# Antennaboard_AndesiteV3Rel.net
KiCad netlist of a schematic drawn in EAGLE
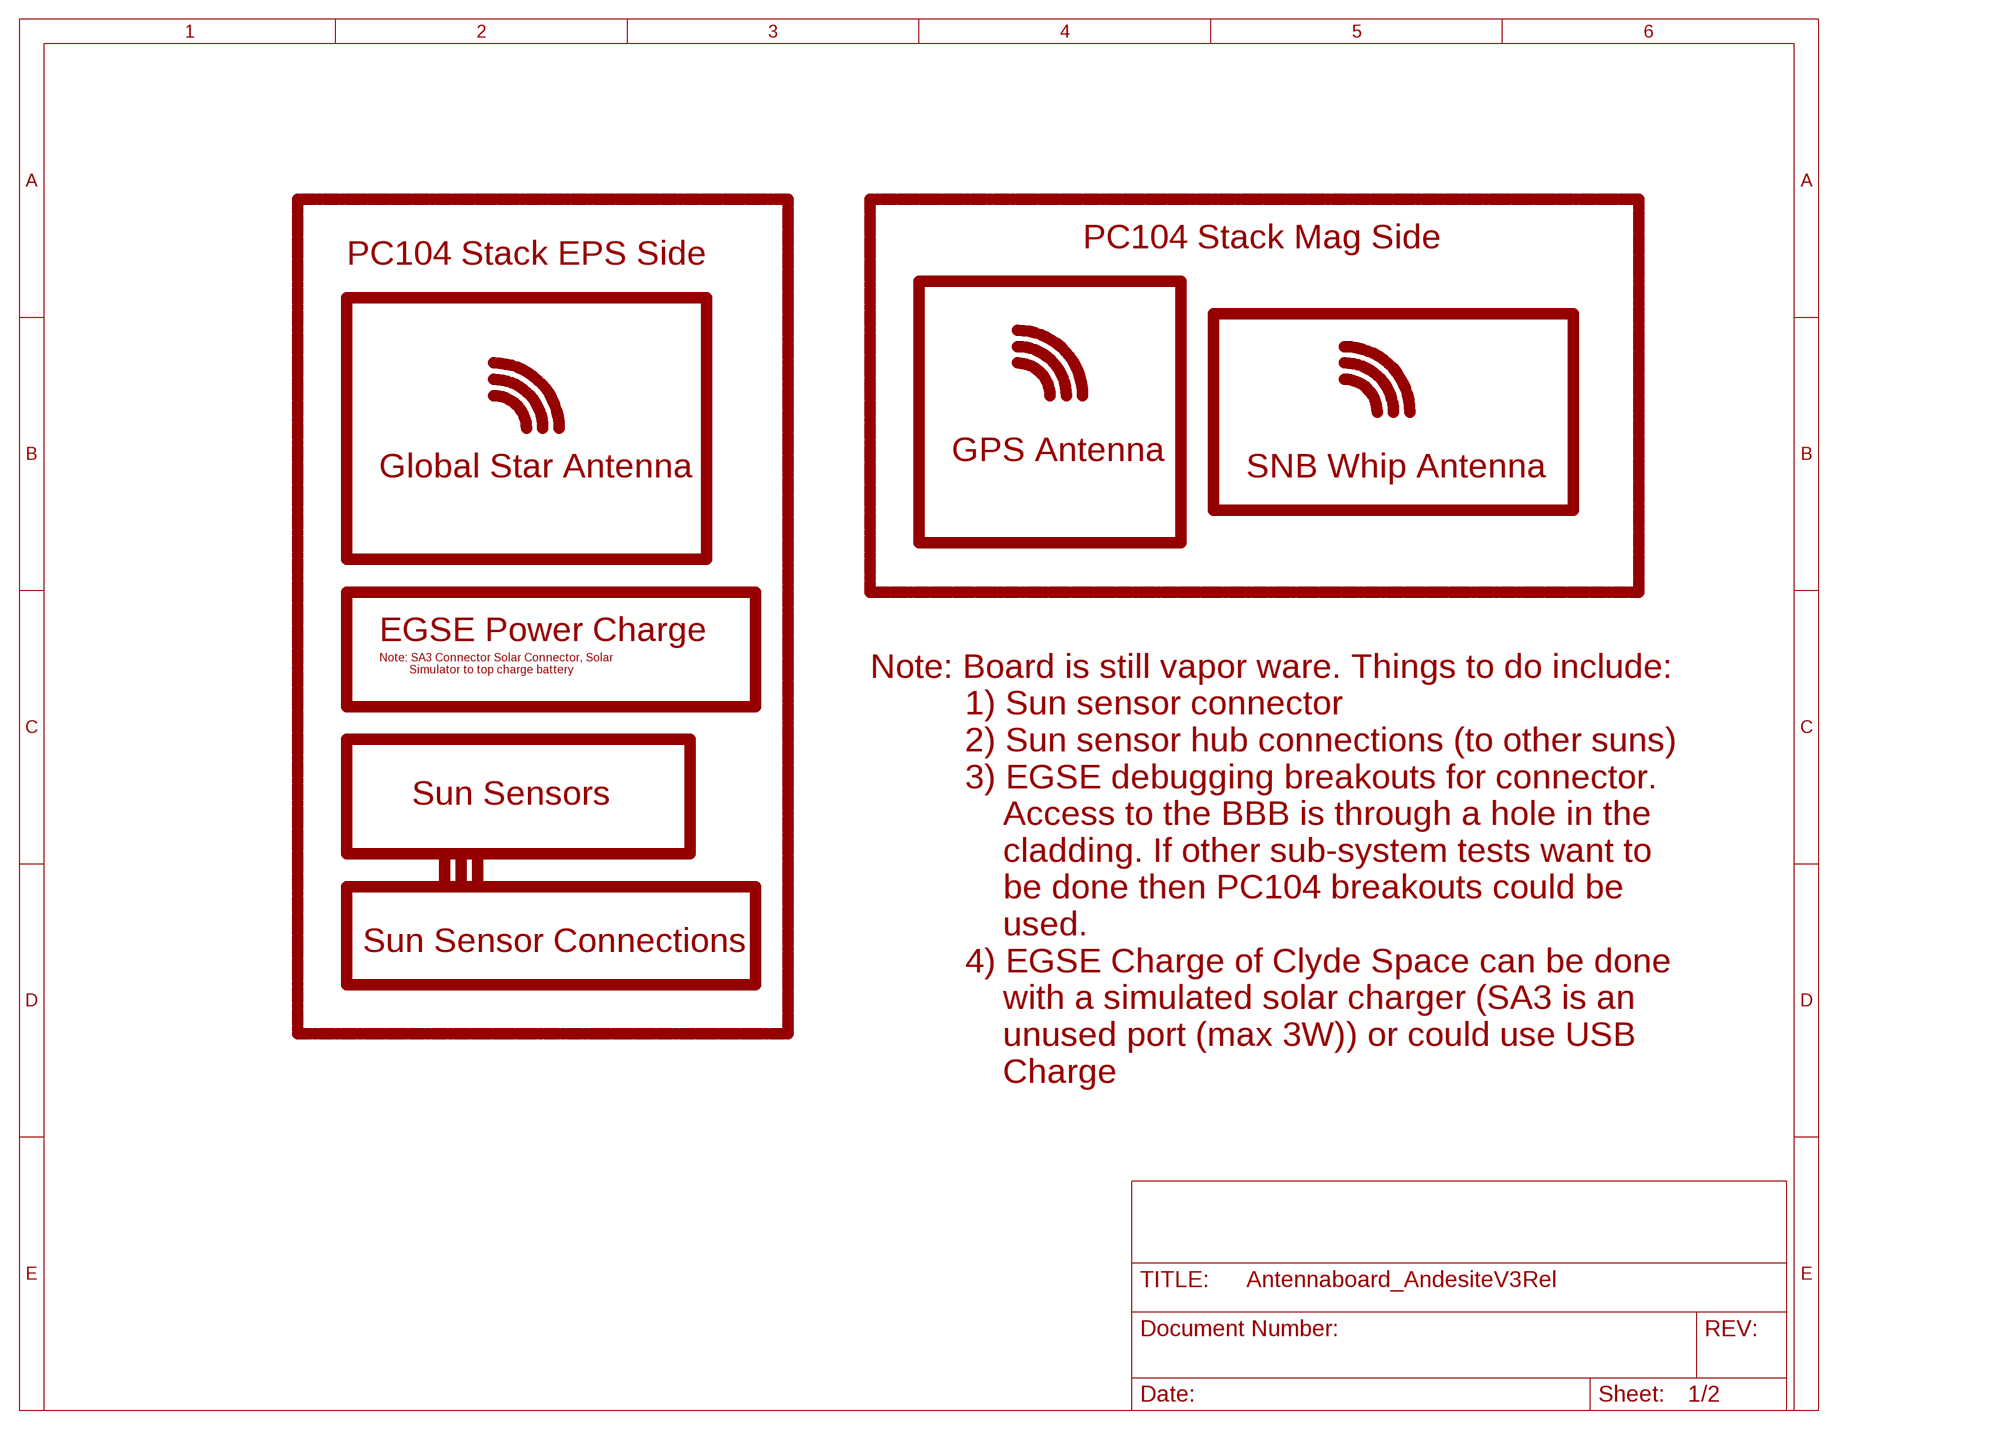
[diagram p0: schematic, sheet 1]
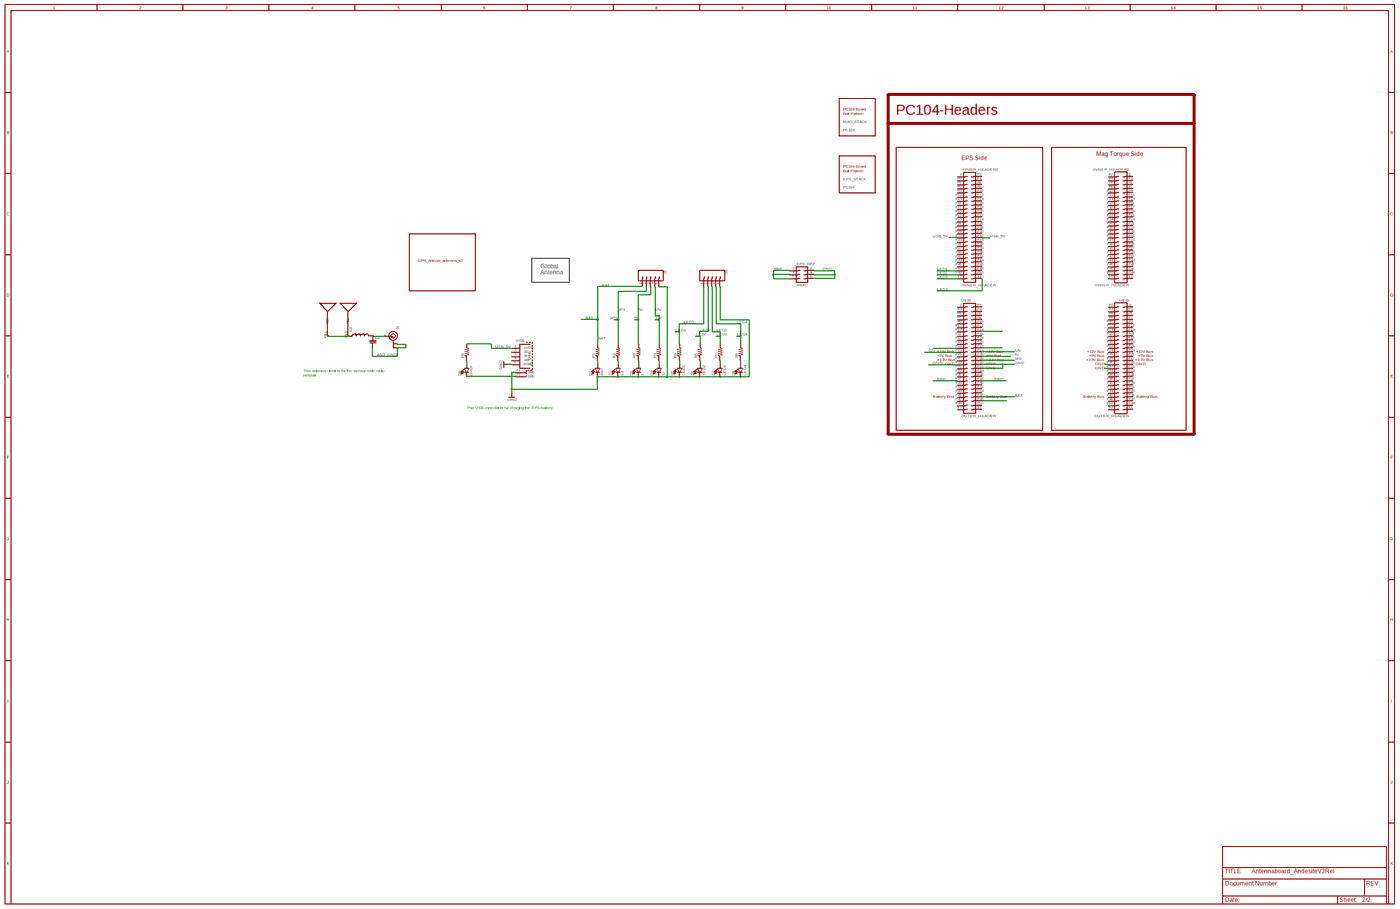
[diagram p1: schematic, sheet 2, overview]
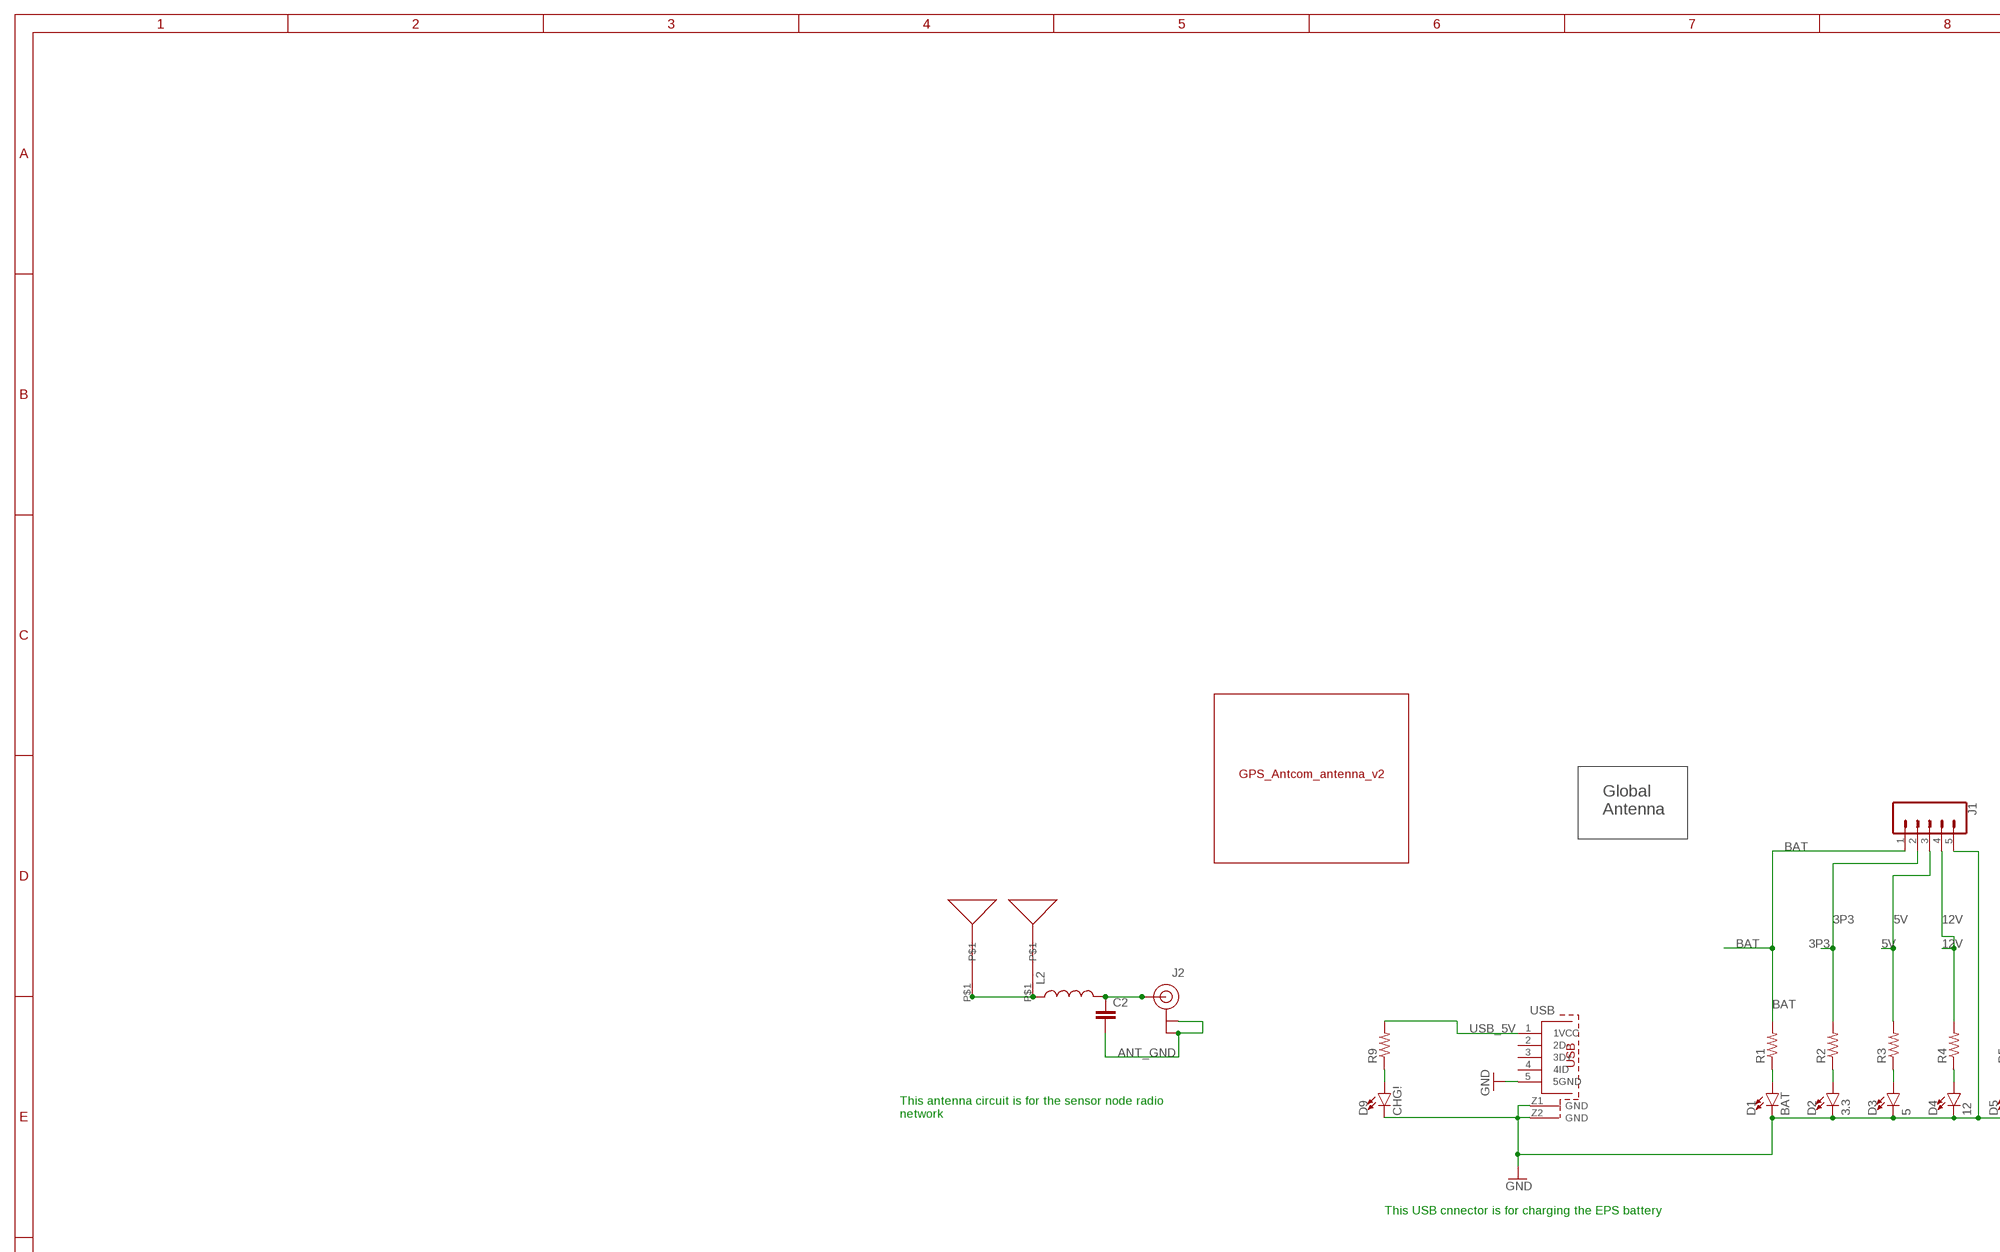
[diagram p2: schematic, sheet 2, part 1 of 4]
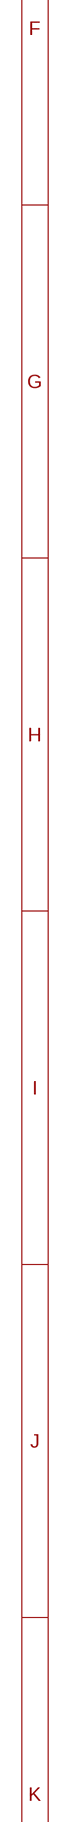
[diagram p3: schematic, sheet 2, part 2 of 4]
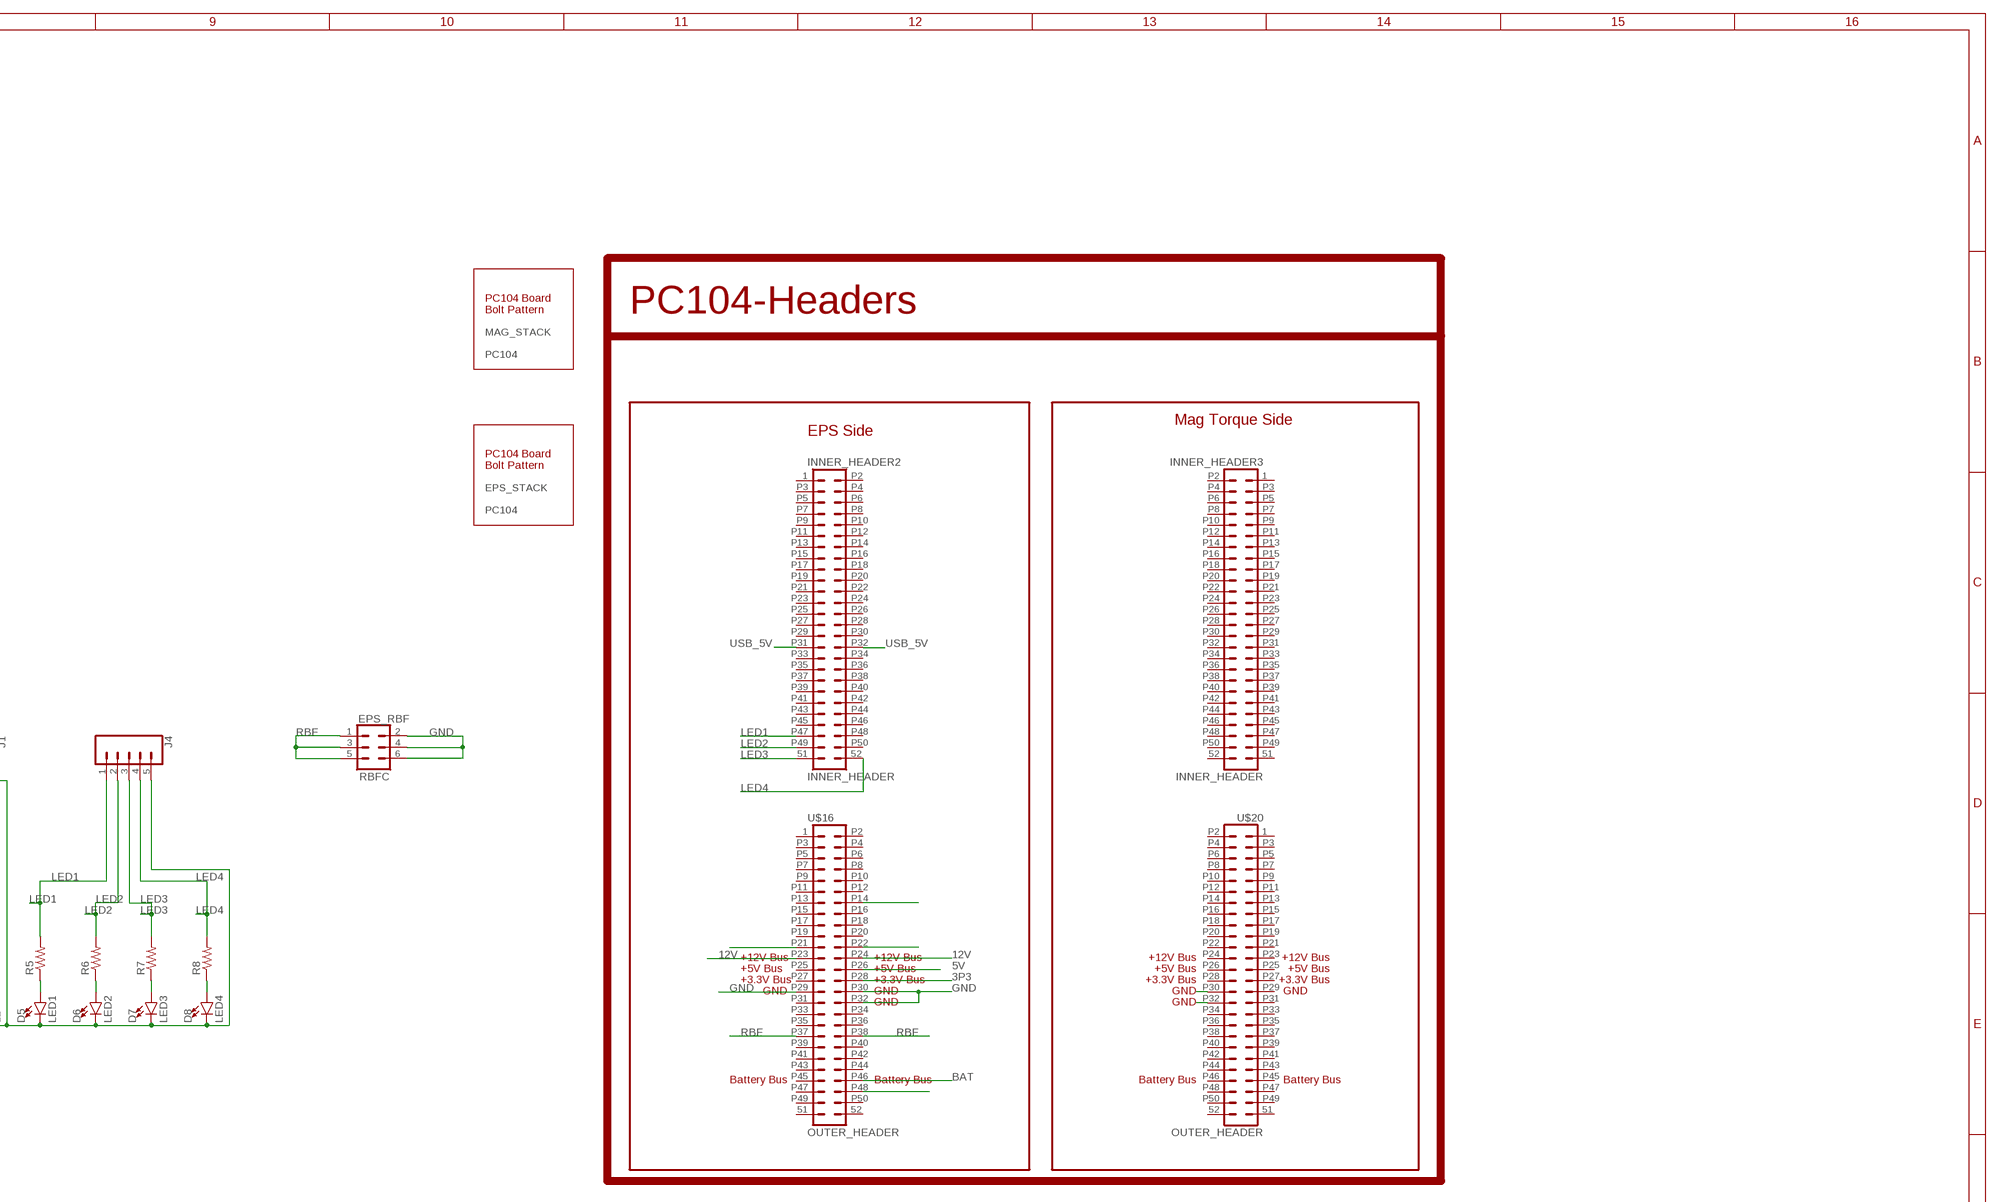
[diagram p4: schematic, sheet 2, part 3 of 4]
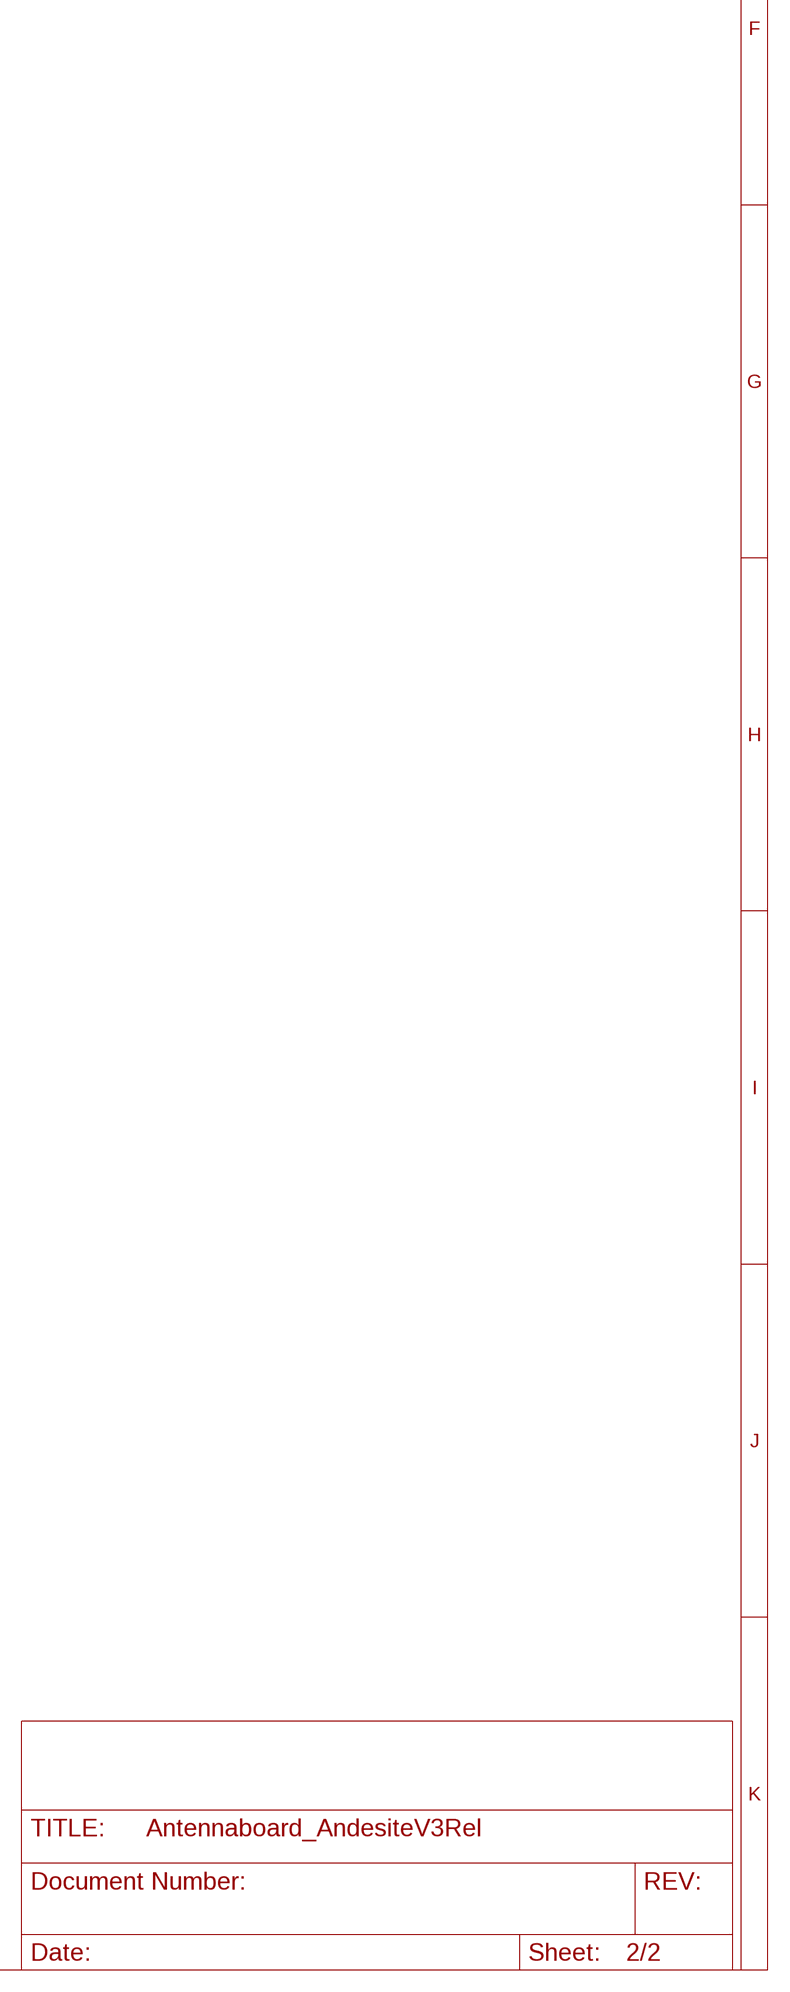
[diagram p5: schematic, sheet 2, part 4 of 4]

(export (version "E")
  (design (tool "Eeschema 10.0.6"))
  (components
    (comp (ref "C2")
      (value "CAP1210")
      (footprint "eagle-import:1210")
      (libsource (lib "eagle-import") (part "CAP1210"))
    )
    (comp (ref "D1")
      (value "BAT")
      (footprint "eagle-import:LED-0603")
      (libsource (lib "eagle-import") (part "LED-RED0603"))
    )
    (comp (ref "D2")
      (value "3.3")
      (footprint "eagle-import:LED-0603")
      (libsource (lib "eagle-import") (part "LED-RED0603"))
    )
    (comp (ref "D3")
      (value "5")
      (footprint "eagle-import:LED-0603")
      (libsource (lib "eagle-import") (part "LED-RED0603"))
    )
    (comp (ref "D4")
      (value "12")
      (footprint "eagle-import:LED-0603")
      (libsource (lib "eagle-import") (part "LED-RED0603"))
    )
    (comp (ref "D5")
      (value "LED1")
      (footprint "eagle-import:LED-0603")
      (libsource (lib "eagle-import") (part "LED-RED0603"))
    )
    (comp (ref "D6")
      (value "LED2")
      (footprint "eagle-import:LED-0603")
      (libsource (lib "eagle-import") (part "LED-RED0603"))
    )
    (comp (ref "D7")
      (value "LED3")
      (footprint "eagle-import:LED-0603")
      (libsource (lib "eagle-import") (part "LED-RED0603"))
    )
    (comp (ref "D8")
      (value "LED4")
      (footprint "eagle-import:LED-0603")
      (libsource (lib "eagle-import") (part "LED-RED0603"))
    )
    (comp (ref "D9")
      (value "CHG!")
      (footprint "eagle-import:LED-0603")
      (libsource (lib "eagle-import") (part "LED-RED0603"))
    )
    (comp (ref "EPS_RBF")
      (value "RBFC")
      (footprint "eagle-import:2X3")
      (libsource (lib "eagle-import") (part "CONN_03X2FEMALE"))
    )
    (comp (ref "EPS_STACK")
      (value "PC104")
      (footprint "eagle-import:PC104")
      (libsource (lib "eagle-import") (part "PC104"))
    )
    (comp (ref "INNER_HEADER2")
      (value "INNER_HEADER")
      (footprint "eagle-import:2X26")
      (libsource (lib "eagle-import") (part "INNER_HEADER"))
    )
    (comp (ref "INNER_HEADER3")
      (value "INNER_HEADER")
      (footprint "eagle-import:2X26")
      (libsource (lib "eagle-import") (part "INNER_HEADER"))
    )
    (comp (ref "J1")
      (value "CONN_05NO_SILK")
      (footprint "eagle-import:1X05_NO_SILK")
      (libsource (lib "eagle-import") (part "CONN_05NO_SILK"))
    )
    (comp (ref "J2")
      (value "U.FL")
      (footprint "eagle-import:U.FL")
      (libsource (lib "eagle-import") (part "U.FL"))
    )
    (comp (ref "J4")
      (value "CONN_05NO_SILK")
      (footprint "eagle-import:1X05_NO_SILK")
      (libsource (lib "eagle-import") (part "CONN_05NO_SILK"))
    )
    (comp (ref "L2")
      (value "INDUCTOR1210")
      (footprint "eagle-import:1210")
      (libsource (lib "eagle-import") (part "INDUCTOR1210"))
    )
    (comp (ref "MAG_STACK")
      (value "PC104")
      (footprint "eagle-import:PC104")
      (libsource (lib "eagle-import") (part "PC104"))
    )
    (comp (ref "R1")
      (value "R-US_R0603")
      (footprint "eagle-import:R0603")
      (libsource (lib "eagle-import") (part "R-US_R0603"))
    )
    (comp (ref "R2")
      (value "R-US_R0603")
      (footprint "eagle-import:R0603")
      (libsource (lib "eagle-import") (part "R-US_R0603"))
    )
    (comp (ref "R3")
      (value "R-US_R0603")
      (footprint "eagle-import:R0603")
      (libsource (lib "eagle-import") (part "R-US_R0603"))
    )
    (comp (ref "R4")
      (value "R-US_R0603")
      (footprint "eagle-import:R0603")
      (libsource (lib "eagle-import") (part "R-US_R0603"))
    )
    (comp (ref "R5")
      (value "R-US_R0603")
      (footprint "eagle-import:R0603")
      (libsource (lib "eagle-import") (part "R-US_R0603"))
    )
    (comp (ref "R6")
      (value "R-US_R0603")
      (footprint "eagle-import:R0603")
      (libsource (lib "eagle-import") (part "R-US_R0603"))
    )
    (comp (ref "R7")
      (value "R-US_R0603")
      (footprint "eagle-import:R0603")
      (libsource (lib "eagle-import") (part "R-US_R0603"))
    )
    (comp (ref "R8")
      (value "R-US_R0603")
      (footprint "eagle-import:R0603")
      (libsource (lib "eagle-import") (part "R-US_R0603"))
    )
    (comp (ref "R9")
      (value "R-US_R0603")
      (footprint "eagle-import:R0603")
      (libsource (lib "eagle-import") (part "R-US_R0603"))
    )
    (comp (ref "U$1")
      (value "ANTENNA")
      (footprint "eagle-import:GLOBAL_ANTENNA")
      (libsource (lib "eagle-import") (part "ANTENNA"))
    )
    (comp (ref "U$2")
      (value "GPS_ANTCOM_ANTENNA")
      (footprint "eagle-import:GPS_ANTCOM_2")
      (libsource (lib "eagle-import") (part "GPS_ANTCOM_ANTENNA"))
    )
    (comp (ref "U$3")
      (value "SNB_ANT")
      (footprint "eagle-import:SLOT")
      (libsource (lib "eagle-import") (part "SNB_ANT"))
    )
    (comp (ref "U$16")
      (value "OUTER_HEADER")
      (footprint "eagle-import:2X26")
      (libsource (lib "eagle-import") (part "OUTER_HEADER"))
    )
    (comp (ref "U$18")
      (value "SNB_ANT")
      (footprint "eagle-import:SLOT")
      (libsource (lib "eagle-import") (part "SNB_ANT"))
    )
    (comp (ref "U$20")
      (value "OUTER_HEADER")
      (footprint "eagle-import:2X26")
      (libsource (lib "eagle-import") (part "OUTER_HEADER"))
    )
    (comp (ref "USB")
      (value "614105150721")
      (footprint "eagle-import:614105150721")
      (libsource (lib "eagle-import") (part "614105150721"))
    )
  )
  (nets
    (net (code "1") (name "3P3") (class "Default")
      (node (ref "J1") (pin "2") (pinfunction "2_2") (pintype "passive"))
      (node (ref "R2") (pin "2") (pinfunction "2_2") (pintype "passive"))
      (node (ref "U$16") (pin "P28") (pinfunction "P28_P28") (pintype "passive"))
    )
    (net (code "2") (name "5V") (class "Default")
      (node (ref "J1") (pin "3") (pinfunction "3_3") (pintype "passive"))
      (node (ref "R3") (pin "2") (pinfunction "2_2") (pintype "passive"))
      (node (ref "U$16") (pin "P26") (pinfunction "26_P26") (pintype "passive"))
    )
    (net (code "3") (name "12V") (class "Default")
      (node (ref "J1") (pin "4") (pinfunction "4_4") (pintype "passive"))
      (node (ref "R4") (pin "2") (pinfunction "2_2") (pintype "passive"))
      (node (ref "U$16") (pin "P23") (pinfunction "23_P23") (pintype "passive"))
      (node (ref "U$16") (pin "P24") (pinfunction "24_P24") (pintype "passive"))
    )
    (net (code "4") (name "ANT_GND") (class "Default")
      (node (ref "C2") (pin "2") (pinfunction "2_2") (pintype "passive"))
      (node (ref "J2") (pin "P$1") (pinfunction "GND_P$1") (pintype "bidirectional"))
      (node (ref "J2") (pin "P$2") (pinfunction "GND_P$2") (pintype "bidirectional"))
    )
    (net (code "5") (name "BAT") (class "Default")
      (node (ref "J1") (pin "1") (pinfunction "1_1") (pintype "passive"))
      (node (ref "R1") (pin "2") (pinfunction "2_2") (pintype "passive"))
      (node (ref "U$16") (pin "P46") (pinfunction "46_P46") (pintype "passive"))
    )
    (net (code "6") (name "GND") (class "Default")
      (node (ref "D1") (pin "C") (pinfunction "C_C") (pintype "passive"))
      (node (ref "D2") (pin "C") (pinfunction "C_C") (pintype "passive"))
      (node (ref "D3") (pin "C") (pinfunction "C_C") (pintype "passive"))
      (node (ref "D4") (pin "C") (pinfunction "C_C") (pintype "passive"))
      (node (ref "D5") (pin "C") (pinfunction "C_C") (pintype "passive"))
      (node (ref "D6") (pin "C") (pinfunction "C_C") (pintype "passive"))
      (node (ref "D7") (pin "C") (pinfunction "C_C") (pintype "passive"))
      (node (ref "D8") (pin "C") (pinfunction "C_C") (pintype "passive"))
      (node (ref "D9") (pin "C") (pinfunction "C_C") (pintype "passive"))
      (node (ref "EPS_RBF") (pin "2") (pinfunction "2_2") (pintype "bidirectional"))
      (node (ref "EPS_RBF") (pin "4") (pinfunction "4_4") (pintype "bidirectional"))
      (node (ref "EPS_RBF") (pin "6") (pinfunction "6_6") (pintype "bidirectional"))
      (node (ref "J1") (pin "5") (pinfunction "5_5") (pintype "passive"))
      (node (ref "J4") (pin "5") (pinfunction "5_5") (pintype "passive"))
      (node (ref "U$16") (pin "P21") (pinfunction "21_P21") (pintype "passive"))
      (node (ref "U$16") (pin "P22") (pinfunction "22_P22") (pintype "passive"))
      (node (ref "U$16") (pin "P29") (pinfunction "P29_P29") (pintype "passive"))
      (node (ref "U$16") (pin "P30") (pinfunction "P30_P30") (pintype "passive"))
      (node (ref "U$16") (pin "P32") (pinfunction "P32_P32") (pintype "passive"))
      (node (ref "U$16") (pin "P48") (pinfunction "48_P48") (pintype "passive"))
      (node (ref "USB") (pin "5") (pinfunction "5GND_5") (pintype "passive"))
      (node (ref "USB") (pin "Z1") (pinfunction "GND_Z1") (pintype "bidirectional"))
      (node (ref "USB") (pin "Z2") (pinfunction "GND_Z2") (pintype "bidirectional"))
    )
    (net (code "7") (name "LED1") (class "Default")
      (node (ref "INNER_HEADER2") (pin "P47") (pinfunction "47_P47") (pintype "passive"))
      (node (ref "J4") (pin "1") (pinfunction "1_1") (pintype "passive"))
      (node (ref "R5") (pin "2") (pinfunction "2_2") (pintype "passive"))
    )
    (net (code "8") (name "LED2") (class "Default")
      (node (ref "INNER_HEADER2") (pin "P49") (pinfunction "49_P49") (pintype "passive"))
      (node (ref "J4") (pin "2") (pinfunction "2_2") (pintype "passive"))
      (node (ref "R6") (pin "2") (pinfunction "2_2") (pintype "passive"))
    )
    (net (code "9") (name "LED3") (class "Default")
      (node (ref "INNER_HEADER2") (pin "51") (pinfunction "51_51") (pintype "passive"))
      (node (ref "J4") (pin "3") (pinfunction "3_3") (pintype "passive"))
      (node (ref "R7") (pin "2") (pinfunction "2_2") (pintype "passive"))
    )
    (net (code "10") (name "LED4") (class "Default")
      (node (ref "INNER_HEADER2") (pin "52") (pinfunction "52_52") (pintype "passive"))
      (node (ref "J4") (pin "4") (pinfunction "4_4") (pintype "passive"))
      (node (ref "R8") (pin "2") (pinfunction "2_2") (pintype "passive"))
    )
    (net (code "11") (name "Net-(D1-PadA)") (class "Default")
      (node (ref "D1") (pin "A") (pinfunction "A_A") (pintype "passive"))
      (node (ref "R1") (pin "1") (pinfunction "1_1") (pintype "passive"))
    )
    (net (code "12") (name "Net-(D2-PadA)") (class "Default")
      (node (ref "D2") (pin "A") (pinfunction "A_A") (pintype "passive"))
      (node (ref "R2") (pin "1") (pinfunction "1_1") (pintype "passive"))
    )
    (net (code "13") (name "Net-(D3-PadA)") (class "Default")
      (node (ref "D3") (pin "A") (pinfunction "A_A") (pintype "passive"))
      (node (ref "R3") (pin "1") (pinfunction "1_1") (pintype "passive"))
    )
    (net (code "14") (name "Net-(D4-PadA)") (class "Default")
      (node (ref "D4") (pin "A") (pinfunction "A_A") (pintype "passive"))
      (node (ref "R4") (pin "1") (pinfunction "1_1") (pintype "passive"))
    )
    (net (code "15") (name "Net-(D5-PadA)") (class "Default")
      (node (ref "D5") (pin "A") (pinfunction "A_A") (pintype "passive"))
      (node (ref "R5") (pin "1") (pinfunction "1_1") (pintype "passive"))
    )
    (net (code "16") (name "Net-(D6-PadA)") (class "Default")
      (node (ref "D6") (pin "A") (pinfunction "A_A") (pintype "passive"))
      (node (ref "R6") (pin "1") (pinfunction "1_1") (pintype "passive"))
    )
    (net (code "17") (name "Net-(D7-PadA)") (class "Default")
      (node (ref "D7") (pin "A") (pinfunction "A_A") (pintype "passive"))
      (node (ref "R7") (pin "1") (pinfunction "1_1") (pintype "passive"))
    )
    (net (code "18") (name "Net-(D8-PadA)") (class "Default")
      (node (ref "D8") (pin "A") (pinfunction "A_A") (pintype "passive"))
      (node (ref "R8") (pin "1") (pinfunction "1_1") (pintype "passive"))
    )
    (net (code "19") (name "Net-(D9-PadA)") (class "Default")
      (node (ref "D9") (pin "A") (pinfunction "A_A") (pintype "passive"))
      (node (ref "R9") (pin "1") (pinfunction "1_1") (pintype "passive"))
    )
    (net (code "20") (name "Net-(J2-SIGNAL)") (class "Default")
      (node (ref "C2") (pin "1") (pinfunction "1_1") (pintype "passive"))
      (node (ref "J2") (pin "P$3") (pinfunction "SIGNAL_P$3") (pintype "bidirectional"))
      (node (ref "L2") (pin "2") (pinfunction "2_2") (pintype "passive"))
    )
    (net (code "21") (name "Net-(L2-Pad1)") (class "Default")
      (node (ref "L2") (pin "1") (pinfunction "1_1") (pintype "passive"))
      (node (ref "U$18") (pin "P$1") (pinfunction "P$1_P$1") (pintype "bidirectional"))
      (node (ref "U$3") (pin "P$1") (pinfunction "P$1_P$1") (pintype "bidirectional"))
    )
    (net (code "22") (name "RBF") (class "Default")
      (node (ref "EPS_RBF") (pin "1") (pinfunction "1_1") (pintype "bidirectional"))
      (node (ref "EPS_RBF") (pin "3") (pinfunction "3_3") (pintype "bidirectional"))
      (node (ref "EPS_RBF") (pin "5") (pinfunction "5_5") (pintype "bidirectional"))
      (node (ref "U$16") (pin "P37") (pinfunction "37_P37") (pintype "passive"))
      (node (ref "U$16") (pin "P38") (pinfunction "38_P38") (pintype "passive"))
    )
    (net (code "23") (name "USB_5V") (class "Default")
      (node (ref "INNER_HEADER2") (pin "P31") (pinfunction "P31_P31") (pintype "passive"))
      (node (ref "INNER_HEADER2") (pin "P32") (pinfunction "P32_P32") (pintype "passive"))
      (node (ref "R9") (pin "2") (pinfunction "2_2") (pintype "passive"))
      (node (ref "USB") (pin "1") (pinfunction "1VCC_1") (pintype "passive"))
    )
    (net (code "24") (name "unconnected-(INNER_HEADER2-2-PadP2)") (class "Default")
      (node (ref "INNER_HEADER2") (pin "P2") (pinfunction "2_P2") (pintype "passive"))
    )
    (net (code "25") (name "unconnected-(INNER_HEADER2-3-PadP3)") (class "Default")
      (node (ref "INNER_HEADER2") (pin "P3") (pinfunction "3_P3") (pintype "passive"))
    )
    (net (code "26") (name "unconnected-(INNER_HEADER2-4-PadP4)") (class "Default")
      (node (ref "INNER_HEADER2") (pin "P4") (pinfunction "4_P4") (pintype "passive"))
    )
    (net (code "27") (name "unconnected-(INNER_HEADER2-5-PadP5)") (class "Default")
      (node (ref "INNER_HEADER2") (pin "P5") (pinfunction "5_P5") (pintype "passive"))
    )
    (net (code "28") (name "unconnected-(INNER_HEADER2-6-PadP6)") (class "Default")
      (node (ref "INNER_HEADER2") (pin "P6") (pinfunction "6_P6") (pintype "passive"))
    )
    (net (code "29") (name "unconnected-(INNER_HEADER2-7-PadP7)") (class "Default")
      (node (ref "INNER_HEADER2") (pin "P7") (pinfunction "7_P7") (pintype "passive"))
    )
    (net (code "30") (name "unconnected-(INNER_HEADER2-8-PadP8)") (class "Default")
      (node (ref "INNER_HEADER2") (pin "P8") (pinfunction "8_P8") (pintype "passive"))
    )
    (net (code "31") (name "unconnected-(INNER_HEADER2-9-PadP9)") (class "Default")
      (node (ref "INNER_HEADER2") (pin "P9") (pinfunction "9_P9") (pintype "passive"))
    )
    (net (code "32") (name "unconnected-(INNER_HEADER2-10-PadP10)") (class "Default")
      (node (ref "INNER_HEADER2") (pin "P10") (pinfunction "10_P10") (pintype "passive"))
    )
    (net (code "33") (name "unconnected-(INNER_HEADER2-11-PadP11)") (class "Default")
      (node (ref "INNER_HEADER2") (pin "P11") (pinfunction "11_P11") (pintype "passive"))
    )
    (net (code "34") (name "unconnected-(INNER_HEADER2-12-PadP12)") (class "Default")
      (node (ref "INNER_HEADER2") (pin "P12") (pinfunction "12_P12") (pintype "passive"))
    )
    (net (code "35") (name "unconnected-(INNER_HEADER2-13-PadP13)") (class "Default")
      (node (ref "INNER_HEADER2") (pin "P13") (pinfunction "13_P13") (pintype "passive"))
    )
    (net (code "36") (name "unconnected-(INNER_HEADER2-14-PadP14)") (class "Default")
      (node (ref "INNER_HEADER2") (pin "P14") (pinfunction "14_P14") (pintype "passive"))
    )
    (net (code "37") (name "unconnected-(INNER_HEADER2-15-PadP15)") (class "Default")
      (node (ref "INNER_HEADER2") (pin "P15") (pinfunction "15_P15") (pintype "passive"))
    )
    (net (code "38") (name "unconnected-(INNER_HEADER2-16-PadP16)") (class "Default")
      (node (ref "INNER_HEADER2") (pin "P16") (pinfunction "16_P16") (pintype "passive"))
    )
    (net (code "39") (name "unconnected-(INNER_HEADER2-17-PadP17)") (class "Default")
      (node (ref "INNER_HEADER2") (pin "P17") (pinfunction "17_P17") (pintype "passive"))
    )
    (net (code "40") (name "unconnected-(INNER_HEADER2-18-PadP18)") (class "Default")
      (node (ref "INNER_HEADER2") (pin "P18") (pinfunction "18_P18") (pintype "passive"))
    )
    (net (code "41") (name "unconnected-(INNER_HEADER2-19-PadP19)") (class "Default")
      (node (ref "INNER_HEADER2") (pin "P19") (pinfunction "19_P19") (pintype "passive"))
    )
    (net (code "42") (name "unconnected-(INNER_HEADER2-20-PadP20)") (class "Default")
      (node (ref "INNER_HEADER2") (pin "P20") (pinfunction "20_P20") (pintype "passive"))
    )
    (net (code "43") (name "unconnected-(INNER_HEADER2-21-PadP21)") (class "Default")
      (node (ref "INNER_HEADER2") (pin "P21") (pinfunction "21_P21") (pintype "passive"))
    )
    (net (code "44") (name "unconnected-(INNER_HEADER2-22-PadP22)") (class "Default")
      (node (ref "INNER_HEADER2") (pin "P22") (pinfunction "22_P22") (pintype "passive"))
    )
    (net (code "45") (name "unconnected-(INNER_HEADER2-23-PadP23)") (class "Default")
      (node (ref "INNER_HEADER2") (pin "P23") (pinfunction "23_P23") (pintype "passive"))
    )
    (net (code "46") (name "unconnected-(INNER_HEADER2-24-PadP24)") (class "Default")
      (node (ref "INNER_HEADER2") (pin "P24") (pinfunction "24_P24") (pintype "passive"))
    )
    (net (code "47") (name "unconnected-(INNER_HEADER2-25-PadP25)") (class "Default")
      (node (ref "INNER_HEADER2") (pin "P25") (pinfunction "25_P25") (pintype "passive"))
    )
    (net (code "48") (name "unconnected-(INNER_HEADER2-26-PadP26)") (class "Default")
      (node (ref "INNER_HEADER2") (pin "P26") (pinfunction "26_P26") (pintype "passive"))
    )
    (net (code "49") (name "unconnected-(INNER_HEADER2-37-PadP37)") (class "Default")
      (node (ref "INNER_HEADER2") (pin "P37") (pinfunction "37_P37") (pintype "passive"))
    )
    (net (code "50") (name "unconnected-(INNER_HEADER2-38-PadP38)") (class "Default")
      (node (ref "INNER_HEADER2") (pin "P38") (pinfunction "38_P38") (pintype "passive"))
    )
    (net (code "51") (name "unconnected-(INNER_HEADER2-39-PadP39)") (class "Default")
      (node (ref "INNER_HEADER2") (pin "P39") (pinfunction "39_P39") (pintype "passive"))
    )
    (net (code "52") (name "unconnected-(INNER_HEADER2-40-PadP40)") (class "Default")
      (node (ref "INNER_HEADER2") (pin "P40") (pinfunction "40_P40") (pintype "passive"))
    )
    (net (code "53") (name "unconnected-(INNER_HEADER2-41-PadP41)") (class "Default")
      (node (ref "INNER_HEADER2") (pin "P41") (pinfunction "41_P41") (pintype "passive"))
    )
    (net (code "54") (name "unconnected-(INNER_HEADER2-42-PadP42)") (class "Default")
      (node (ref "INNER_HEADER2") (pin "P42") (pinfunction "42_P42") (pintype "passive"))
    )
    (net (code "55") (name "unconnected-(INNER_HEADER2-43-PadP43)") (class "Default")
      (node (ref "INNER_HEADER2") (pin "P43") (pinfunction "43_P43") (pintype "passive"))
    )
    (net (code "56") (name "unconnected-(INNER_HEADER2-44-PadP44)") (class "Default")
      (node (ref "INNER_HEADER2") (pin "P44") (pinfunction "44_P44") (pintype "passive"))
    )
    (net (code "57") (name "unconnected-(INNER_HEADER2-45-PadP45)") (class "Default")
      (node (ref "INNER_HEADER2") (pin "P45") (pinfunction "45_P45") (pintype "passive"))
    )
    (net (code "58") (name "unconnected-(INNER_HEADER2-46-PadP46)") (class "Default")
      (node (ref "INNER_HEADER2") (pin "P46") (pinfunction "46_P46") (pintype "passive"))
    )
    (net (code "59") (name "unconnected-(INNER_HEADER2-48-PadP48)") (class "Default")
      (node (ref "INNER_HEADER2") (pin "P48") (pinfunction "48_P48") (pintype "passive"))
    )
    (net (code "60") (name "unconnected-(INNER_HEADER2-50-PadP50)") (class "Default")
      (node (ref "INNER_HEADER2") (pin "P50") (pinfunction "50_P50") (pintype "passive"))
    )
    (net (code "61") (name "unconnected-(INNER_HEADER2-Pad1)") (class "Default")
      (node (ref "INNER_HEADER2") (pin "1") (pinfunction "1_1") (pintype "passive"))
    )
    (net (code "62") (name "unconnected-(INNER_HEADER2-PadP27)") (class "Default")
      (node (ref "INNER_HEADER2") (pin "P27") (pinfunction "P27_P27") (pintype "passive"))
    )
    (net (code "63") (name "unconnected-(INNER_HEADER2-PadP28)") (class "Default")
      (node (ref "INNER_HEADER2") (pin "P28") (pinfunction "P28_P28") (pintype "passive"))
    )
    (net (code "64") (name "unconnected-(INNER_HEADER2-PadP29)") (class "Default")
      (node (ref "INNER_HEADER2") (pin "P29") (pinfunction "P29_P29") (pintype "passive"))
    )
    (net (code "65") (name "unconnected-(INNER_HEADER2-PadP30)") (class "Default")
      (node (ref "INNER_HEADER2") (pin "P30") (pinfunction "P30_P30") (pintype "passive"))
    )
    (net (code "66") (name "unconnected-(INNER_HEADER2-PadP33)") (class "Default")
      (node (ref "INNER_HEADER2") (pin "P33") (pinfunction "P33_P33") (pintype "passive"))
    )
    (net (code "67") (name "unconnected-(INNER_HEADER2-PadP34)") (class "Default")
      (node (ref "INNER_HEADER2") (pin "P34") (pinfunction "P34_P34") (pintype "passive"))
    )
    (net (code "68") (name "unconnected-(INNER_HEADER2-PadP35)") (class "Default")
      (node (ref "INNER_HEADER2") (pin "P35") (pinfunction "P35_P35") (pintype "passive"))
    )
    (net (code "69") (name "unconnected-(INNER_HEADER2-PadP36)") (class "Default")
      (node (ref "INNER_HEADER2") (pin "P36") (pinfunction "P36_P36") (pintype "passive"))
    )
    (net (code "70") (name "unconnected-(INNER_HEADER3-2-PadP2)") (class "Default")
      (node (ref "INNER_HEADER3") (pin "P2") (pinfunction "2_P2") (pintype "passive"))
    )
    (net (code "71") (name "unconnected-(INNER_HEADER3-3-PadP3)") (class "Default")
      (node (ref "INNER_HEADER3") (pin "P3") (pinfunction "3_P3") (pintype "passive"))
    )
    (net (code "72") (name "unconnected-(INNER_HEADER3-4-PadP4)") (class "Default")
      (node (ref "INNER_HEADER3") (pin "P4") (pinfunction "4_P4") (pintype "passive"))
    )
    (net (code "73") (name "unconnected-(INNER_HEADER3-5-PadP5)") (class "Default")
      (node (ref "INNER_HEADER3") (pin "P5") (pinfunction "5_P5") (pintype "passive"))
    )
    (net (code "74") (name "unconnected-(INNER_HEADER3-6-PadP6)") (class "Default")
      (node (ref "INNER_HEADER3") (pin "P6") (pinfunction "6_P6") (pintype "passive"))
    )
    (net (code "75") (name "unconnected-(INNER_HEADER3-7-PadP7)") (class "Default")
      (node (ref "INNER_HEADER3") (pin "P7") (pinfunction "7_P7") (pintype "passive"))
    )
    (net (code "76") (name "unconnected-(INNER_HEADER3-8-PadP8)") (class "Default")
      (node (ref "INNER_HEADER3") (pin "P8") (pinfunction "8_P8") (pintype "passive"))
    )
    (net (code "77") (name "unconnected-(INNER_HEADER3-9-PadP9)") (class "Default")
      (node (ref "INNER_HEADER3") (pin "P9") (pinfunction "9_P9") (pintype "passive"))
    )
    (net (code "78") (name "unconnected-(INNER_HEADER3-10-PadP10)") (class "Default")
      (node (ref "INNER_HEADER3") (pin "P10") (pinfunction "10_P10") (pintype "passive"))
    )
    (net (code "79") (name "unconnected-(INNER_HEADER3-11-PadP11)") (class "Default")
      (node (ref "INNER_HEADER3") (pin "P11") (pinfunction "11_P11") (pintype "passive"))
    )
    (net (code "80") (name "unconnected-(INNER_HEADER3-12-PadP12)") (class "Default")
      (node (ref "INNER_HEADER3") (pin "P12") (pinfunction "12_P12") (pintype "passive"))
    )
    (net (code "81") (name "unconnected-(INNER_HEADER3-13-PadP13)") (class "Default")
      (node (ref "INNER_HEADER3") (pin "P13") (pinfunction "13_P13") (pintype "passive"))
    )
    (net (code "82") (name "unconnected-(INNER_HEADER3-14-PadP14)") (class "Default")
      (node (ref "INNER_HEADER3") (pin "P14") (pinfunction "14_P14") (pintype "passive"))
    )
    (net (code "83") (name "unconnected-(INNER_HEADER3-15-PadP15)") (class "Default")
      (node (ref "INNER_HEADER3") (pin "P15") (pinfunction "15_P15") (pintype "passive"))
    )
    (net (code "84") (name "unconnected-(INNER_HEADER3-16-PadP16)") (class "Default")
      (node (ref "INNER_HEADER3") (pin "P16") (pinfunction "16_P16") (pintype "passive"))
    )
    (net (code "85") (name "unconnected-(INNER_HEADER3-17-PadP17)") (class "Default")
      (node (ref "INNER_HEADER3") (pin "P17") (pinfunction "17_P17") (pintype "passive"))
    )
    (net (code "86") (name "unconnected-(INNER_HEADER3-18-PadP18)") (class "Default")
      (node (ref "INNER_HEADER3") (pin "P18") (pinfunction "18_P18") (pintype "passive"))
    )
    (net (code "87") (name "unconnected-(INNER_HEADER3-19-PadP19)") (class "Default")
      (node (ref "INNER_HEADER3") (pin "P19") (pinfunction "19_P19") (pintype "passive"))
    )
    (net (code "88") (name "unconnected-(INNER_HEADER3-20-PadP20)") (class "Default")
      (node (ref "INNER_HEADER3") (pin "P20") (pinfunction "20_P20") (pintype "passive"))
    )
    (net (code "89") (name "unconnected-(INNER_HEADER3-21-PadP21)") (class "Default")
      (node (ref "INNER_HEADER3") (pin "P21") (pinfunction "21_P21") (pintype "passive"))
    )
    (net (code "90") (name "unconnected-(INNER_HEADER3-22-PadP22)") (class "Default")
      (node (ref "INNER_HEADER3") (pin "P22") (pinfunction "22_P22") (pintype "passive"))
    )
    (net (code "91") (name "unconnected-(INNER_HEADER3-23-PadP23)") (class "Default")
      (node (ref "INNER_HEADER3") (pin "P23") (pinfunction "23_P23") (pintype "passive"))
    )
    (net (code "92") (name "unconnected-(INNER_HEADER3-24-PadP24)") (class "Default")
      (node (ref "INNER_HEADER3") (pin "P24") (pinfunction "24_P24") (pintype "passive"))
    )
    (net (code "93") (name "unconnected-(INNER_HEADER3-25-PadP25)") (class "Default")
      (node (ref "INNER_HEADER3") (pin "P25") (pinfunction "25_P25") (pintype "passive"))
    )
    (net (code "94") (name "unconnected-(INNER_HEADER3-26-PadP26)") (class "Default")
      (node (ref "INNER_HEADER3") (pin "P26") (pinfunction "26_P26") (pintype "passive"))
    )
    (net (code "95") (name "unconnected-(INNER_HEADER3-37-PadP37)") (class "Default")
      (node (ref "INNER_HEADER3") (pin "P37") (pinfunction "37_P37") (pintype "passive"))
    )
    (net (code "96") (name "unconnected-(INNER_HEADER3-38-PadP38)") (class "Default")
      (node (ref "INNER_HEADER3") (pin "P38") (pinfunction "38_P38") (pintype "passive"))
    )
    (net (code "97") (name "unconnected-(INNER_HEADER3-39-PadP39)") (class "Default")
      (node (ref "INNER_HEADER3") (pin "P39") (pinfunction "39_P39") (pintype "passive"))
    )
    (net (code "98") (name "unconnected-(INNER_HEADER3-40-PadP40)") (class "Default")
      (node (ref "INNER_HEADER3") (pin "P40") (pinfunction "40_P40") (pintype "passive"))
    )
    (net (code "99") (name "unconnected-(INNER_HEADER3-41-PadP41)") (class "Default")
      (node (ref "INNER_HEADER3") (pin "P41") (pinfunction "41_P41") (pintype "passive"))
    )
    (net (code "100") (name "unconnected-(INNER_HEADER3-42-PadP42)") (class "Default")
      (node (ref "INNER_HEADER3") (pin "P42") (pinfunction "42_P42") (pintype "passive"))
    )
    (net (code "101") (name "unconnected-(INNER_HEADER3-43-PadP43)") (class "Default")
      (node (ref "INNER_HEADER3") (pin "P43") (pinfunction "43_P43") (pintype "passive"))
    )
    (net (code "102") (name "unconnected-(INNER_HEADER3-44-PadP44)") (class "Default")
      (node (ref "INNER_HEADER3") (pin "P44") (pinfunction "44_P44") (pintype "passive"))
    )
    (net (code "103") (name "unconnected-(INNER_HEADER3-45-PadP45)") (class "Default")
      (node (ref "INNER_HEADER3") (pin "P45") (pinfunction "45_P45") (pintype "passive"))
    )
    (net (code "104") (name "unconnected-(INNER_HEADER3-46-PadP46)") (class "Default")
      (node (ref "INNER_HEADER3") (pin "P46") (pinfunction "46_P46") (pintype "passive"))
    )
    (net (code "105") (name "unconnected-(INNER_HEADER3-47-PadP47)") (class "Default")
      (node (ref "INNER_HEADER3") (pin "P47") (pinfunction "47_P47") (pintype "passive"))
    )
    (net (code "106") (name "unconnected-(INNER_HEADER3-48-PadP48)") (class "Default")
      (node (ref "INNER_HEADER3") (pin "P48") (pinfunction "48_P48") (pintype "passive"))
    )
    (net (code "107") (name "unconnected-(INNER_HEADER3-49-PadP49)") (class "Default")
      (node (ref "INNER_HEADER3") (pin "P49") (pinfunction "49_P49") (pintype "passive"))
    )
    (net (code "108") (name "unconnected-(INNER_HEADER3-50-PadP50)") (class "Default")
      (node (ref "INNER_HEADER3") (pin "P50") (pinfunction "50_P50") (pintype "passive"))
    )
    (net (code "109") (name "unconnected-(INNER_HEADER3-Pad1)") (class "Default")
      (node (ref "INNER_HEADER3") (pin "1") (pinfunction "1_1") (pintype "passive"))
    )
    (net (code "110") (name "unconnected-(INNER_HEADER3-Pad51)") (class "Default")
      (node (ref "INNER_HEADER3") (pin "51") (pinfunction "51_51") (pintype "passive"))
    )
    (net (code "111") (name "unconnected-(INNER_HEADER3-Pad52)") (class "Default")
      (node (ref "INNER_HEADER3") (pin "52") (pinfunction "52_52") (pintype "passive"))
    )
    (net (code "112") (name "unconnected-(INNER_HEADER3-PadP27)") (class "Default")
      (node (ref "INNER_HEADER3") (pin "P27") (pinfunction "P27_P27") (pintype "passive"))
    )
    (net (code "113") (name "unconnected-(INNER_HEADER3-PadP28)") (class "Default")
      (node (ref "INNER_HEADER3") (pin "P28") (pinfunction "P28_P28") (pintype "passive"))
    )
    (net (code "114") (name "unconnected-(INNER_HEADER3-PadP29)") (class "Default")
      (node (ref "INNER_HEADER3") (pin "P29") (pinfunction "P29_P29") (pintype "passive"))
    )
    (net (code "115") (name "unconnected-(INNER_HEADER3-PadP30)") (class "Default")
      (node (ref "INNER_HEADER3") (pin "P30") (pinfunction "P30_P30") (pintype "passive"))
    )
    (net (code "116") (name "unconnected-(INNER_HEADER3-PadP31)") (class "Default")
      (node (ref "INNER_HEADER3") (pin "P31") (pinfunction "P31_P31") (pintype "passive"))
    )
    (net (code "117") (name "unconnected-(INNER_HEADER3-PadP32)") (class "Default")
      (node (ref "INNER_HEADER3") (pin "P32") (pinfunction "P32_P32") (pintype "passive"))
    )
    (net (code "118") (name "unconnected-(INNER_HEADER3-PadP33)") (class "Default")
      (node (ref "INNER_HEADER3") (pin "P33") (pinfunction "P33_P33") (pintype "passive"))
    )
    (net (code "119") (name "unconnected-(INNER_HEADER3-PadP34)") (class "Default")
      (node (ref "INNER_HEADER3") (pin "P34") (pinfunction "P34_P34") (pintype "passive"))
    )
    (net (code "120") (name "unconnected-(INNER_HEADER3-PadP35)") (class "Default")
      (node (ref "INNER_HEADER3") (pin "P35") (pinfunction "P35_P35") (pintype "passive"))
    )
    (net (code "121") (name "unconnected-(INNER_HEADER3-PadP36)") (class "Default")
      (node (ref "INNER_HEADER3") (pin "P36") (pinfunction "P36_P36") (pintype "passive"))
    )
    (net (code "122") (name "unconnected-(U$16-2-PadP2)") (class "Default")
      (node (ref "U$16") (pin "P2") (pinfunction "2_P2") (pintype "passive"))
    )
    (net (code "123") (name "unconnected-(U$16-3-PadP3)") (class "Default")
      (node (ref "U$16") (pin "P3") (pinfunction "3_P3") (pintype "passive"))
    )
    (net (code "124") (name "unconnected-(U$16-4-PadP4)") (class "Default")
      (node (ref "U$16") (pin "P4") (pinfunction "4_P4") (pintype "passive"))
    )
    (net (code "125") (name "unconnected-(U$16-5-PadP5)") (class "Default")
      (node (ref "U$16") (pin "P5") (pinfunction "5_P5") (pintype "passive"))
    )
    (net (code "126") (name "unconnected-(U$16-6-PadP6)") (class "Default")
      (node (ref "U$16") (pin "P6") (pinfunction "6_P6") (pintype "passive"))
    )
    (net (code "127") (name "unconnected-(U$16-7-PadP7)") (class "Default")
      (node (ref "U$16") (pin "P7") (pinfunction "7_P7") (pintype "passive"))
    )
    (net (code "128") (name "unconnected-(U$16-8-PadP8)") (class "Default")
      (node (ref "U$16") (pin "P8") (pinfunction "8_P8") (pintype "passive"))
    )
    (net (code "129") (name "unconnected-(U$16-9-PadP9)") (class "Default")
      (node (ref "U$16") (pin "P9") (pinfunction "9_P9") (pintype "passive"))
    )
    (net (code "130") (name "unconnected-(U$16-10-PadP10)") (class "Default")
      (node (ref "U$16") (pin "P10") (pinfunction "10_P10") (pintype "passive"))
    )
    (net (code "131") (name "unconnected-(U$16-11-PadP11)") (class "Default")
      (node (ref "U$16") (pin "P11") (pinfunction "11_P11") (pintype "passive"))
    )
    (net (code "132") (name "unconnected-(U$16-12-PadP12)") (class "Default")
      (node (ref "U$16") (pin "P12") (pinfunction "12_P12") (pintype "passive"))
    )
    (net (code "133") (name "unconnected-(U$16-13-PadP13)") (class "Default")
      (node (ref "U$16") (pin "P13") (pinfunction "13_P13") (pintype "passive"))
    )
    (net (code "134") (name "unconnected-(U$16-14-PadP14)") (class "Default")
      (node (ref "U$16") (pin "P14") (pinfunction "14_P14") (pintype "passive"))
    )
    (net (code "135") (name "unconnected-(U$16-15-PadP15)") (class "Default")
      (node (ref "U$16") (pin "P15") (pinfunction "15_P15") (pintype "passive"))
    )
    (net (code "136") (name "unconnected-(U$16-16-PadP16)") (class "Default")
      (node (ref "U$16") (pin "P16") (pinfunction "16_P16") (pintype "passive"))
    )
    (net (code "137") (name "unconnected-(U$16-17-PadP17)") (class "Default")
      (node (ref "U$16") (pin "P17") (pinfunction "17_P17") (pintype "passive"))
    )
    (net (code "138") (name "unconnected-(U$16-18-PadP18)") (class "Default")
      (node (ref "U$16") (pin "P18") (pinfunction "18_P18") (pintype "passive"))
    )
    (net (code "139") (name "unconnected-(U$16-19-PadP19)") (class "Default")
      (node (ref "U$16") (pin "P19") (pinfunction "19_P19") (pintype "passive"))
    )
    (net (code "140") (name "unconnected-(U$16-20-PadP20)") (class "Default")
      (node (ref "U$16") (pin "P20") (pinfunction "20_P20") (pintype "passive"))
    )
    (net (code "141") (name "unconnected-(U$16-25-PadP25)") (class "Default")
      (node (ref "U$16") (pin "P25") (pinfunction "25_P25") (pintype "passive"))
    )
    (net (code "142") (name "unconnected-(U$16-39-PadP39)") (class "Default")
      (node (ref "U$16") (pin "P39") (pinfunction "39_P39") (pintype "passive"))
    )
    (net (code "143") (name "unconnected-(U$16-40-PadP40)") (class "Default")
      (node (ref "U$16") (pin "P40") (pinfunction "40_P40") (pintype "passive"))
    )
    (net (code "144") (name "unconnected-(U$16-41-PadP41)") (class "Default")
      (node (ref "U$16") (pin "P41") (pinfunction "41_P41") (pintype "passive"))
    )
    (net (code "145") (name "unconnected-(U$16-42-PadP42)") (class "Default")
      (node (ref "U$16") (pin "P42") (pinfunction "42_P42") (pintype "passive"))
    )
    (net (code "146") (name "unconnected-(U$16-43-PadP43)") (class "Default")
      (node (ref "U$16") (pin "P43") (pinfunction "43_P43") (pintype "passive"))
    )
    (net (code "147") (name "unconnected-(U$16-44-PadP44)") (class "Default")
      (node (ref "U$16") (pin "P44") (pinfunction "44_P44") (pintype "passive"))
    )
    (net (code "148") (name "unconnected-(U$16-45-PadP45)") (class "Default")
      (node (ref "U$16") (pin "P45") (pinfunction "45_P45") (pintype "passive"))
    )
    (net (code "149") (name "unconnected-(U$16-47-PadP47)") (class "Default")
      (node (ref "U$16") (pin "P47") (pinfunction "47_P47") (pintype "passive"))
    )
    (net (code "150") (name "unconnected-(U$16-49-PadP49)") (class "Default")
      (node (ref "U$16") (pin "P49") (pinfunction "49_P49") (pintype "passive"))
    )
    (net (code "151") (name "unconnected-(U$16-50-PadP50)") (class "Default")
      (node (ref "U$16") (pin "P50") (pinfunction "50_P50") (pintype "passive"))
    )
    (net (code "152") (name "unconnected-(U$16-Pad1)") (class "Default")
      (node (ref "U$16") (pin "1") (pinfunction "1_1") (pintype "passive"))
    )
    (net (code "153") (name "unconnected-(U$16-Pad51)") (class "Default")
      (node (ref "U$16") (pin "51") (pinfunction "51_51") (pintype "passive"))
    )
    (net (code "154") (name "unconnected-(U$16-Pad52)") (class "Default")
      (node (ref "U$16") (pin "52") (pinfunction "52_52") (pintype "passive"))
    )
    (net (code "155") (name "unconnected-(U$16-PadP27)") (class "Default")
      (node (ref "U$16") (pin "P27") (pinfunction "P27_P27") (pintype "passive"))
    )
    (net (code "156") (name "unconnected-(U$16-PadP31)") (class "Default")
      (node (ref "U$16") (pin "P31") (pinfunction "P31_P31") (pintype "passive"))
    )
    (net (code "157") (name "unconnected-(U$16-PadP33)") (class "Default")
      (node (ref "U$16") (pin "P33") (pinfunction "P33_P33") (pintype "passive"))
    )
    (net (code "158") (name "unconnected-(U$16-PadP34)") (class "Default")
      (node (ref "U$16") (pin "P34") (pinfunction "P34_P34") (pintype "passive"))
    )
    (net (code "159") (name "unconnected-(U$16-PadP35)") (class "Default")
      (node (ref "U$16") (pin "P35") (pinfunction "P35_P35") (pintype "passive"))
    )
    (net (code "160") (name "unconnected-(U$16-PadP36)") (class "Default")
      (node (ref "U$16") (pin "P36") (pinfunction "P36_P36") (pintype "passive"))
    )
    (net (code "161") (name "unconnected-(U$20-2-PadP2)") (class "Default")
      (node (ref "U$20") (pin "P2") (pinfunction "2_P2") (pintype "passive"))
    )
    (net (code "162") (name "unconnected-(U$20-3-PadP3)") (class "Default")
      (node (ref "U$20") (pin "P3") (pinfunction "3_P3") (pintype "passive"))
    )
    (net (code "163") (name "unconnected-(U$20-4-PadP4)") (class "Default")
      (node (ref "U$20") (pin "P4") (pinfunction "4_P4") (pintype "passive"))
    )
    (net (code "164") (name "unconnected-(U$20-5-PadP5)") (class "Default")
      (node (ref "U$20") (pin "P5") (pinfunction "5_P5") (pintype "passive"))
    )
    (net (code "165") (name "unconnected-(U$20-6-PadP6)") (class "Default")
      (node (ref "U$20") (pin "P6") (pinfunction "6_P6") (pintype "passive"))
    )
    (net (code "166") (name "unconnected-(U$20-7-PadP7)") (class "Default")
      (node (ref "U$20") (pin "P7") (pinfunction "7_P7") (pintype "passive"))
    )
    (net (code "167") (name "unconnected-(U$20-8-PadP8)") (class "Default")
      (node (ref "U$20") (pin "P8") (pinfunction "8_P8") (pintype "passive"))
    )
    (net (code "168") (name "unconnected-(U$20-9-PadP9)") (class "Default")
      (node (ref "U$20") (pin "P9") (pinfunction "9_P9") (pintype "passive"))
    )
    (net (code "169") (name "unconnected-(U$20-10-PadP10)") (class "Default")
      (node (ref "U$20") (pin "P10") (pinfunction "10_P10") (pintype "passive"))
    )
    (net (code "170") (name "unconnected-(U$20-11-PadP11)") (class "Default")
      (node (ref "U$20") (pin "P11") (pinfunction "11_P11") (pintype "passive"))
    )
    (net (code "171") (name "unconnected-(U$20-12-PadP12)") (class "Default")
      (node (ref "U$20") (pin "P12") (pinfunction "12_P12") (pintype "passive"))
    )
    (net (code "172") (name "unconnected-(U$20-13-PadP13)") (class "Default")
      (node (ref "U$20") (pin "P13") (pinfunction "13_P13") (pintype "passive"))
    )
    (net (code "173") (name "unconnected-(U$20-14-PadP14)") (class "Default")
      (node (ref "U$20") (pin "P14") (pinfunction "14_P14") (pintype "passive"))
    )
    (net (code "174") (name "unconnected-(U$20-15-PadP15)") (class "Default")
      (node (ref "U$20") (pin "P15") (pinfunction "15_P15") (pintype "passive"))
    )
    (net (code "175") (name "unconnected-(U$20-16-PadP16)") (class "Default")
      (node (ref "U$20") (pin "P16") (pinfunction "16_P16") (pintype "passive"))
    )
    (net (code "176") (name "unconnected-(U$20-17-PadP17)") (class "Default")
      (node (ref "U$20") (pin "P17") (pinfunction "17_P17") (pintype "passive"))
    )
    (net (code "177") (name "unconnected-(U$20-18-PadP18)") (class "Default")
      (node (ref "U$20") (pin "P18") (pinfunction "18_P18") (pintype "passive"))
    )
    (net (code "178") (name "unconnected-(U$20-19-PadP19)") (class "Default")
      (node (ref "U$20") (pin "P19") (pinfunction "19_P19") (pintype "passive"))
    )
    (net (code "179") (name "unconnected-(U$20-20-PadP20)") (class "Default")
      (node (ref "U$20") (pin "P20") (pinfunction "20_P20") (pintype "passive"))
    )
    (net (code "180") (name "unconnected-(U$20-21-PadP21)") (class "Default")
      (node (ref "U$20") (pin "P21") (pinfunction "21_P21") (pintype "passive"))
    )
    (net (code "181") (name "unconnected-(U$20-22-PadP22)") (class "Default")
      (node (ref "U$20") (pin "P22") (pinfunction "22_P22") (pintype "passive"))
    )
    (net (code "182") (name "unconnected-(U$20-23-PadP23)") (class "Default")
      (node (ref "U$20") (pin "P23") (pinfunction "23_P23") (pintype "passive"))
    )
    (net (code "183") (name "unconnected-(U$20-24-PadP24)") (class "Default")
      (node (ref "U$20") (pin "P24") (pinfunction "24_P24") (pintype "passive"))
    )
    (net (code "184") (name "unconnected-(U$20-25-PadP25)") (class "Default")
      (node (ref "U$20") (pin "P25") (pinfunction "25_P25") (pintype "passive"))
    )
    (net (code "185") (name "unconnected-(U$20-26-PadP26)") (class "Default")
      (node (ref "U$20") (pin "P26") (pinfunction "26_P26") (pintype "passive"))
    )
    (net (code "186") (name "unconnected-(U$20-37-PadP37)") (class "Default")
      (node (ref "U$20") (pin "P37") (pinfunction "37_P37") (pintype "passive"))
    )
    (net (code "187") (name "unconnected-(U$20-38-PadP38)") (class "Default")
      (node (ref "U$20") (pin "P38") (pinfunction "38_P38") (pintype "passive"))
    )
    (net (code "188") (name "unconnected-(U$20-39-PadP39)") (class "Default")
      (node (ref "U$20") (pin "P39") (pinfunction "39_P39") (pintype "passive"))
    )
    (net (code "189") (name "unconnected-(U$20-40-PadP40)") (class "Default")
      (node (ref "U$20") (pin "P40") (pinfunction "40_P40") (pintype "passive"))
    )
    (net (code "190") (name "unconnected-(U$20-41-PadP41)") (class "Default")
      (node (ref "U$20") (pin "P41") (pinfunction "41_P41") (pintype "passive"))
    )
    (net (code "191") (name "unconnected-(U$20-42-PadP42)") (class "Default")
      (node (ref "U$20") (pin "P42") (pinfunction "42_P42") (pintype "passive"))
    )
    (net (code "192") (name "unconnected-(U$20-43-PadP43)") (class "Default")
      (node (ref "U$20") (pin "P43") (pinfunction "43_P43") (pintype "passive"))
    )
    (net (code "193") (name "unconnected-(U$20-44-PadP44)") (class "Default")
      (node (ref "U$20") (pin "P44") (pinfunction "44_P44") (pintype "passive"))
    )
    (net (code "194") (name "unconnected-(U$20-45-PadP45)") (class "Default")
      (node (ref "U$20") (pin "P45") (pinfunction "45_P45") (pintype "passive"))
    )
    (net (code "195") (name "unconnected-(U$20-46-PadP46)") (class "Default")
      (node (ref "U$20") (pin "P46") (pinfunction "46_P46") (pintype "passive"))
    )
    (net (code "196") (name "unconnected-(U$20-47-PadP47)") (class "Default")
      (node (ref "U$20") (pin "P47") (pinfunction "47_P47") (pintype "passive"))
    )
    (net (code "197") (name "unconnected-(U$20-48-PadP48)") (class "Default")
      (node (ref "U$20") (pin "P48") (pinfunction "48_P48") (pintype "passive"))
    )
    (net (code "198") (name "unconnected-(U$20-49-PadP49)") (class "Default")
      (node (ref "U$20") (pin "P49") (pinfunction "49_P49") (pintype "passive"))
    )
    (net (code "199") (name "unconnected-(U$20-50-PadP50)") (class "Default")
      (node (ref "U$20") (pin "P50") (pinfunction "50_P50") (pintype "passive"))
    )
    (net (code "200") (name "unconnected-(U$20-Pad1)") (class "Default")
      (node (ref "U$20") (pin "1") (pinfunction "1_1") (pintype "passive"))
    )
    (net (code "201") (name "unconnected-(U$20-Pad51)") (class "Default")
      (node (ref "U$20") (pin "51") (pinfunction "51_51") (pintype "passive"))
    )
    (net (code "202") (name "unconnected-(U$20-Pad52)") (class "Default")
      (node (ref "U$20") (pin "52") (pinfunction "52_52") (pintype "passive"))
    )
    (net (code "203") (name "unconnected-(U$20-PadP27)") (class "Default")
      (node (ref "U$20") (pin "P27") (pinfunction "P27_P27") (pintype "passive"))
    )
    (net (code "204") (name "unconnected-(U$20-PadP28)") (class "Default")
      (node (ref "U$20") (pin "P28") (pinfunction "P28_P28") (pintype "passive"))
    )
    (net (code "205") (name "unconnected-(U$20-PadP29)") (class "Default")
      (node (ref "U$20") (pin "P29") (pinfunction "P29_P29") (pintype "passive"))
    )
    (net (code "206") (name "unconnected-(U$20-PadP30)") (class "Default")
      (node (ref "U$20") (pin "P30") (pinfunction "P30_P30") (pintype "passive"))
    )
    (net (code "207") (name "unconnected-(U$20-PadP31)") (class "Default")
      (node (ref "U$20") (pin "P31") (pinfunction "P31_P31") (pintype "passive"))
    )
    (net (code "208") (name "unconnected-(U$20-PadP32)") (class "Default")
      (node (ref "U$20") (pin "P32") (pinfunction "P32_P32") (pintype "passive"))
    )
    (net (code "209") (name "unconnected-(U$20-PadP33)") (class "Default")
      (node (ref "U$20") (pin "P33") (pinfunction "P33_P33") (pintype "passive"))
    )
    (net (code "210") (name "unconnected-(U$20-PadP34)") (class "Default")
      (node (ref "U$20") (pin "P34") (pinfunction "P34_P34") (pintype "passive"))
    )
    (net (code "211") (name "unconnected-(U$20-PadP35)") (class "Default")
      (node (ref "U$20") (pin "P35") (pinfunction "P35_P35") (pintype "passive"))
    )
    (net (code "212") (name "unconnected-(U$20-PadP36)") (class "Default")
      (node (ref "U$20") (pin "P36") (pinfunction "P36_P36") (pintype "passive"))
    )
    (net (code "213") (name "unconnected-(USB-2D--Pad2)") (class "Default")
      (node (ref "USB") (pin "2") (pinfunction "2D-_2") (pintype "passive"))
    )
    (net (code "214") (name "unconnected-(USB-3D+-Pad3)") (class "Default")
      (node (ref "USB") (pin "3") (pinfunction "3D+_3") (pintype "passive"))
    )
    (net (code "215") (name "unconnected-(USB-4ID-Pad4)") (class "Default")
      (node (ref "USB") (pin "4") (pinfunction "4ID_4") (pintype "passive"))
    )
  )
)
